# Sheet_1_2021-11-24.net
KiCad netlist of a schematic drawn in Altium Designer
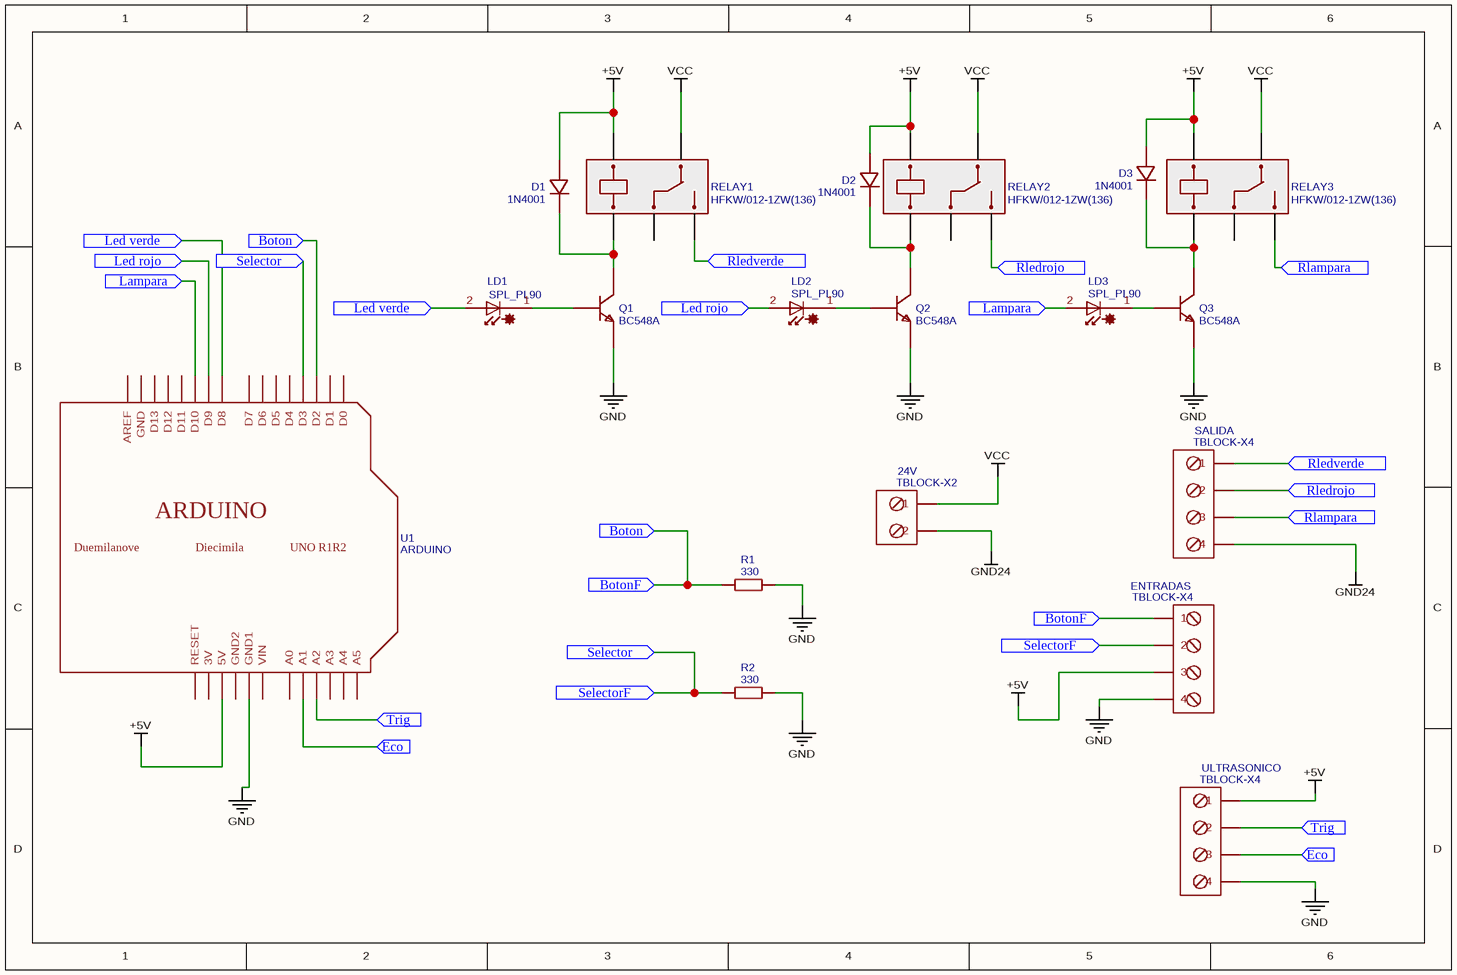
[diagram p0: Sheet_1_2021-11-24.schdoc]

(export (version "E")
  (design (tool "Eeschema 10.0.6"))
  (components
    (comp (ref "24V")
      (value "TBLOCK-X2")
      (fields (field (name "CONTRIBUTOR") "ahmedyerli"))
      (libsource (lib "altium-import") (part "root_0_TBLOCK-X2_"))
    )
    (comp (ref "D1")
      (value "1N4001")
      (fields (field (name "BOM_SUPPLIER PART") "C82804"))
      (libsource (lib "altium-import") (part "root_1_1N4001_"))
    )
    (comp (ref "D2")
      (value "1N4001")
      (fields (field (name "BOM_SUPPLIER PART") "C82804"))
      (libsource (lib "altium-import") (part "root_1_1N4001_"))
    )
    (comp (ref "D3")
      (value "1N4001")
      (fields (field (name "BOM_SUPPLIER PART") "C82804"))
      (libsource (lib "altium-import") (part "root_1_1N4001_"))
    )
    (comp (ref "ENTRADAS")
      (value "TBLOCK-X4")
      (fields (field (name "CONTRIBUTOR") "ahmedyerli"))
      (libsource (lib "") (part "root_0_TBLOCK-X4__1"))
    )
    (comp (ref "LD1")
      (value "SPL_PL90")
      (fields (field (name "CONTRIBUTOR") "KiCAD"))
      (libsource (lib "altium-import") (part "root_2_SPL_PL90_"))
    )
    (comp (ref "LD2")
      (value "SPL_PL90")
      (fields (field (name "CONTRIBUTOR") "KiCAD"))
      (libsource (lib "altium-import") (part "root_2_SPL_PL90_"))
    )
    (comp (ref "LD3")
      (value "SPL_PL90")
      (fields (field (name "CONTRIBUTOR") "KiCAD"))
      (libsource (lib "altium-import") (part "root_2_SPL_PL90_"))
    )
    (comp (ref "Q1")
      (value "BC548A")
      (description "Amplifier Transistor NPN Silicon")
      (libsource (lib "altium-import") (part "root_0_BC548A_"))
    )
    (comp (ref "Q2")
      (value "BC548A")
      (description "Amplifier Transistor NPN Silicon")
      (libsource (lib "altium-import") (part "root_0_BC548A_"))
    )
    (comp (ref "Q3")
      (value "BC548A")
      (description "Amplifier Transistor NPN Silicon")
      (libsource (lib "altium-import") (part "root_0_BC548A_"))
    )
    (comp (ref "R1")
      (value "330")
      (fields (field (name "BOM_SUPPLIER PART") "C10322") (field (name "CONTRIBUTOR") "LCSC"))
      (libsource (lib "altium-import") (part "root_0_330_"))
    )
    (comp (ref "R2")
      (value "330")
      (fields (field (name "BOM_SUPPLIER PART") "C10322") (field (name "CONTRIBUTOR") "LCSC"))
      (libsource (lib "altium-import") (part "root_0_330_"))
    )
    (comp (ref "RELAY1")
      (value "HFKW/012-1ZW(136)")
      (libsource (lib "altium-import") (part "root_0_HFKW/012-1ZW(136)_"))
    )
    (comp (ref "RELAY2")
      (value "HFKW/012-1ZW(136)")
      (libsource (lib "altium-import") (part "root_0_HFKW/012-1ZW(136)_"))
    )
    (comp (ref "RELAY3")
      (value "HFKW/012-1ZW(136)")
      (libsource (lib "altium-import") (part "root_0_HFKW/012-1ZW(136)_"))
    )
    (comp (ref "SALIDA")
      (value "TBLOCK-X4")
      (fields (field (name "CONTRIBUTOR") "ahmedyerli"))
      (libsource (lib "altium-import") (part "root_0_TBLOCK-X4_"))
    )
    (comp (ref "U1")
      (value "ARDUINO")
      (fields (field (name "CONTRIBUTOR") "Adafruit"))
      (libsource (lib "altium-import") (part "root_0_ARDUINO_"))
    )
    (comp (ref "ULTRASONICO")
      (value "TBLOCK-X4")
      (fields (field (name "CONTRIBUTOR") "ahmedyerli"))
      (libsource (lib "altium-import") (part "root_0_TBLOCK-X4_"))
    )
  )
  (nets
    (net (code "1") (name "+5V") (class "Default")
      (node (ref "D1") (pin "2") (pinfunction "A_2") (pintype "passive"))
      (node (ref "D2") (pin "2") (pinfunction "A_2") (pintype "passive"))
      (node (ref "D3") (pin "2") (pinfunction "A_2") (pintype "passive"))
      (node (ref "ENTRADAS") (pin "3") (pinfunction "3_3") (pintype "passive"))
      (node (ref "RELAY1") (pin "1") (pinfunction "1_1") (pintype "passive"))
      (node (ref "RELAY2") (pin "1") (pinfunction "1_1") (pintype "passive"))
      (node (ref "RELAY3") (pin "1") (pinfunction "1_1") (pintype "passive"))
      (node (ref "U1") (pin "5V") (pinfunction "5V_5V") (pintype "passive"))
      (node (ref "ULTRASONICO") (pin "1") (pinfunction "1_1") (pintype "passive"))
    )
    (net (code "2") (name "/Boton") (class "Default")
      (node (ref "ENTRADAS") (pin "1") (pinfunction "1_1") (pintype "passive"))
      (node (ref "R1") (pin "1") (pinfunction "1_1") (pintype "passive"))
      (node (ref "U1") (pin "D2") (pinfunction "D2_D2") (pintype "passive"))
    )
    (net (code "3") (name "/Eco") (class "Default")
      (node (ref "U1") (pin "A1") (pinfunction "A1_A1") (pintype "passive"))
      (node (ref "ULTRASONICO") (pin "3") (pinfunction "3_3") (pintype "passive"))
    )
    (net (code "4") (name "/Lampara") (class "Default")
      (node (ref "LD3") (pin "2") (pinfunction "A_2") (pintype "passive"))
      (node (ref "U1") (pin "D10") (pinfunction "D10_D10") (pintype "passive"))
    )
    (net (code "5") (name "/Led rojo") (class "Default")
      (node (ref "LD2") (pin "2") (pinfunction "A_2") (pintype "passive"))
      (node (ref "U1") (pin "D9") (pinfunction "D9_D9") (pintype "passive"))
    )
    (net (code "6") (name "/Led verde") (class "Default")
      (node (ref "LD1") (pin "2") (pinfunction "A_2") (pintype "passive"))
      (node (ref "U1") (pin "D8") (pinfunction "D8_D8") (pintype "passive"))
    )
    (net (code "7") (name "/Rlampara") (class "Default")
      (node (ref "RELAY3") (pin "5") (pinfunction "5_5") (pintype "passive"))
      (node (ref "SALIDA") (pin "3") (pinfunction "3_3") (pintype "passive"))
    )
    (net (code "8") (name "/Rledrojo") (class "Default")
      (node (ref "RELAY2") (pin "5") (pinfunction "5_5") (pintype "passive"))
      (node (ref "SALIDA") (pin "2") (pinfunction "2_2") (pintype "passive"))
    )
    (net (code "9") (name "/Rledverde") (class "Default")
      (node (ref "RELAY1") (pin "5") (pinfunction "5_5") (pintype "passive"))
      (node (ref "SALIDA") (pin "1") (pinfunction "1_1") (pintype "passive"))
    )
    (net (code "10") (name "/Selector") (class "Default")
      (node (ref "ENTRADAS") (pin "2") (pinfunction "2_2") (pintype "passive"))
      (node (ref "R2") (pin "1") (pinfunction "1_1") (pintype "passive"))
      (node (ref "U1") (pin "D3") (pinfunction "D3_D3") (pintype "passive"))
    )
    (net (code "11") (name "/Trig") (class "Default")
      (node (ref "U1") (pin "A2") (pinfunction "A2_A2") (pintype "passive"))
      (node (ref "ULTRASONICO") (pin "2") (pinfunction "2_2") (pintype "passive"))
    )
    (net (code "12") (name "GND") (class "Default")
      (node (ref "ENTRADAS") (pin "4") (pinfunction "4_4") (pintype "passive"))
      (node (ref "Q1") (pin "3") (pinfunction "E_3") (pintype "passive"))
      (node (ref "Q2") (pin "3") (pinfunction "E_3") (pintype "passive"))
      (node (ref "Q3") (pin "3") (pinfunction "E_3") (pintype "passive"))
      (node (ref "R1") (pin "2") (pinfunction "2_2") (pintype "passive"))
      (node (ref "R2") (pin "2") (pinfunction "2_2") (pintype "passive"))
      (node (ref "U1") (pin "GND1") (pinfunction "GND1_GND1") (pintype "passive"))
      (node (ref "ULTRASONICO") (pin "4") (pinfunction "4_4") (pintype "passive"))
    )
    (net (code "13") (name "GND24") (class "Default")
      (node (ref "24V") (pin "2") (pinfunction "2_2") (pintype "passive"))
      (node (ref "SALIDA") (pin "4") (pinfunction "4_4") (pintype "passive"))
    )
    (net (code "14") (name "Net-(D1-K)") (class "Default")
      (node (ref "D1") (pin "1") (pinfunction "K_1") (pintype "passive"))
      (node (ref "Q1") (pin "1") (pinfunction "C_1") (pintype "passive"))
      (node (ref "RELAY1") (pin "2") (pinfunction "2_2") (pintype "passive"))
    )
    (net (code "15") (name "Net-(D2-K)") (class "Default")
      (node (ref "D2") (pin "1") (pinfunction "K_1") (pintype "passive"))
      (node (ref "Q2") (pin "1") (pinfunction "C_1") (pintype "passive"))
      (node (ref "RELAY2") (pin "2") (pinfunction "2_2") (pintype "passive"))
    )
    (net (code "16") (name "Net-(D3-K)") (class "Default")
      (node (ref "D3") (pin "1") (pinfunction "K_1") (pintype "passive"))
      (node (ref "Q3") (pin "1") (pinfunction "C_1") (pintype "passive"))
      (node (ref "RELAY3") (pin "2") (pinfunction "2_2") (pintype "passive"))
    )
    (net (code "17") (name "Net-(LD1-C)") (class "Default")
      (node (ref "LD1") (pin "1") (pinfunction "C_1") (pintype "passive"))
      (node (ref "Q1") (pin "2") (pinfunction "B_2") (pintype "passive"))
    )
    (net (code "18") (name "Net-(LD2-C)") (class "Default")
      (node (ref "LD2") (pin "1") (pinfunction "C_1") (pintype "passive"))
      (node (ref "Q2") (pin "2") (pinfunction "B_2") (pintype "passive"))
    )
    (net (code "19") (name "Net-(LD3-C)") (class "Default")
      (node (ref "LD3") (pin "1") (pinfunction "C_1") (pintype "passive"))
      (node (ref "Q3") (pin "2") (pinfunction "B_2") (pintype "passive"))
    )
    (net (code "20") (name "VCC") (class "Default")
      (node (ref "24V") (pin "1") (pinfunction "1_1") (pintype "passive"))
      (node (ref "RELAY1") (pin "3") (pinfunction "3_3") (pintype "passive"))
      (node (ref "RELAY2") (pin "3") (pinfunction "3_3") (pintype "passive"))
      (node (ref "RELAY3") (pin "3") (pinfunction "3_3") (pintype "passive"))
    )
    (net (code "21") (name "unconnected-(RELAY1-Pad4)") (class "Default")
      (node (ref "RELAY1") (pin "4") (pinfunction "4_4") (pintype "passive"))
    )
    (net (code "22") (name "unconnected-(RELAY2-Pad4)") (class "Default")
      (node (ref "RELAY2") (pin "4") (pinfunction "4_4") (pintype "passive"))
    )
    (net (code "23") (name "unconnected-(RELAY3-Pad4)") (class "Default")
      (node (ref "RELAY3") (pin "4") (pinfunction "4_4") (pintype "passive"))
    )
    (net (code "24") (name "unconnected-(U1-Pad3V)") (class "Default")
      (node (ref "U1") (pin "3V") (pinfunction "3V_3V") (pintype "passive"))
    )
    (net (code "25") (name "unconnected-(U1-PadA0)") (class "Default")
      (node (ref "U1") (pin "A0") (pinfunction "A0_A0") (pintype "passive"))
    )
    (net (code "26") (name "unconnected-(U1-PadA3)") (class "Default")
      (node (ref "U1") (pin "A3") (pinfunction "A3_A3") (pintype "passive"))
    )
    (net (code "27") (name "unconnected-(U1-PadA4)") (class "Default")
      (node (ref "U1") (pin "A4") (pinfunction "A4_A4") (pintype "passive"))
    )
    (net (code "28") (name "unconnected-(U1-PadA5)") (class "Default")
      (node (ref "U1") (pin "A5") (pinfunction "A5_A5") (pintype "passive"))
    )
    (net (code "29") (name "unconnected-(U1-PadAREF)") (class "Default")
      (node (ref "U1") (pin "AREF") (pinfunction "AREF_AREF") (pintype "passive"))
    )
    (net (code "30") (name "unconnected-(U1-PadD0)") (class "Default")
      (node (ref "U1") (pin "D0") (pinfunction "D0_D0") (pintype "passive"))
    )
    (net (code "31") (name "unconnected-(U1-PadD1)") (class "Default")
      (node (ref "U1") (pin "D1") (pinfunction "D1_D1") (pintype "passive"))
    )
    (net (code "32") (name "unconnected-(U1-PadD4)") (class "Default")
      (node (ref "U1") (pin "D4") (pinfunction "D4_D4") (pintype "passive"))
    )
    (net (code "33") (name "unconnected-(U1-PadD5)") (class "Default")
      (node (ref "U1") (pin "D5") (pinfunction "D5_D5") (pintype "passive"))
    )
    (net (code "34") (name "unconnected-(U1-PadD6)") (class "Default")
      (node (ref "U1") (pin "D6") (pinfunction "D6_D6") (pintype "passive"))
    )
    (net (code "35") (name "unconnected-(U1-PadD7)") (class "Default")
      (node (ref "U1") (pin "D7") (pinfunction "D7_D7") (pintype "passive"))
    )
    (net (code "36") (name "unconnected-(U1-PadD11)") (class "Default")
      (node (ref "U1") (pin "D11") (pinfunction "D11_D11") (pintype "passive"))
    )
    (net (code "37") (name "unconnected-(U1-PadD12)") (class "Default")
      (node (ref "U1") (pin "D12") (pinfunction "D12_D12") (pintype "passive"))
    )
    (net (code "38") (name "unconnected-(U1-PadD13)") (class "Default")
      (node (ref "U1") (pin "D13") (pinfunction "D13_D13") (pintype "passive"))
    )
    (net (code "39") (name "unconnected-(U1-PadGND)") (class "Default")
      (node (ref "U1") (pin "GND") (pinfunction "GND_GND") (pintype "passive"))
    )
    (net (code "40") (name "unconnected-(U1-PadGND2)") (class "Default")
      (node (ref "U1") (pin "GND2") (pinfunction "GND2_GND2") (pintype "passive"))
    )
    (net (code "41") (name "unconnected-(U1-PadRESET)") (class "Default")
      (node (ref "U1") (pin "RESET") (pinfunction "RESET_RESET") (pintype "passive"))
    )
    (net (code "42") (name "unconnected-(U1-PadVIN)") (class "Default")
      (node (ref "U1") (pin "VIN") (pinfunction "VIN_VIN") (pintype "passive"))
    )
  )
)
